# POWER_PCie.net
KiCad netlist of a schematic drawn in Altium Designer
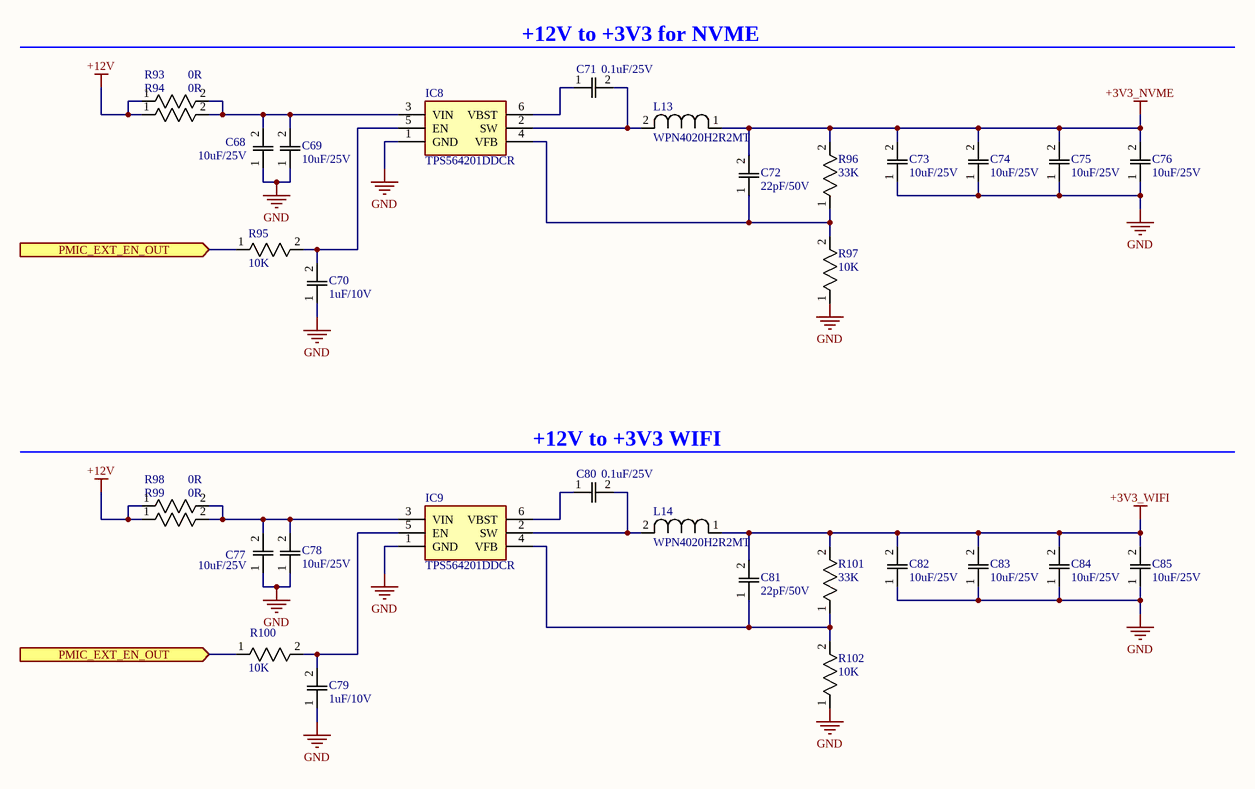
[diagram p0: POWER_PCie.SchDoc]

(export (version "E")
  (design (tool "Eeschema 10.0.6"))
  (components
    (comp (ref "C68")
      (value "10uF/25V")
      (footprint "CAPC220145_88N_KEM")
      (description "10uF / 25 VDC, +85degC, X5R Dielec, +/-10% ¦ KEMET C0805C106K3PACTU 0805")
      (fields
        (field (name "MANUFACTURER") "KEMET")
        (field (name "MANUFACTURER PART NUMBER") "C0805C106K3PACTU")
      )
      (libsource (lib "C0805C106K3PACTU") (part "C0805C106K3PACTU"))
    )
    (comp (ref "C69")
      (value "10uF/25V")
      (footprint "CAPC220145_88N_KEM")
      (description "10uF / 25 VDC, +85degC, X5R Dielec, +/-10% ¦ KEMET C0805C106K3PACTU 0805")
      (fields
        (field (name "MANUFACTURER") "KEMET")
        (field (name "MANUFACTURER PART NUMBER") "C0805C106K3PACTU")
      )
      (libsource (lib "C0805C106K3PACTU") (part "C0805C106K3PACTU"))
    )
    (comp (ref "C70")
      (value "1uF/10V")
      (footprint "CAPC220145_88N_KEM")
      (description "Multilayer Ceramic Capacitors MLCC - SMD/SMT 10V 1uF X7R 0805 10%")
      (fields
        (field (name "MANUFACTURER") "KEMET")
        (field (name "MANUFACTURER PART NUMBER") "C0805C105K8RACTU")
      )
      (libsource (lib "C0805C105K8RACTU") (part "C0805C105K8RACTU"))
    )
    (comp (ref "C71")
      (value "0.1uF/25V")
      (footprint "CAPC220145_88N_KEM")
      (description "0.1uF 25V X7R 10% SMD 0805 125C Plastic T/R")
      (fields
        (field (name "MANUFACTURER") "KEMET")
        (field (name "MANUFACTURER PART NUMBER") "C0805C104K3RACTU")
      )
      (libsource (lib "C0805C104K3RACTU") (part "C0805C104K3RACTU"))
    )
    (comp (ref "C72")
      (value "22pF/50V")
      (footprint "CAPC220145_88N_KEM")
      (description "Cap Ceramic 22pF 50V X7R 5% Pad SMD 0805 125°C T/R")
      (fields
        (field (name "MANUFACTURER") "KEMET")
        (field (name "MANUFACTURER PART NUMBER") "C0805C220J5RACTU")
      )
      (libsource (lib "C0805C220J5RACTU") (part "C0805C220J5RACTU"))
    )
    (comp (ref "C73")
      (value "10uF/25V")
      (footprint "CAPC220145_88N_KEM")
      (description "10uF / 25 VDC, +85degC, X5R Dielec, +/-10% ¦ KEMET C0805C106K3PACTU 0805")
      (fields
        (field (name "MANUFACTURER") "KEMET")
        (field (name "MANUFACTURER PART NUMBER") "C0805C106K3PACTU")
      )
      (libsource (lib "C0805C106K3PACTU") (part "C0805C106K3PACTU"))
    )
    (comp (ref "C74")
      (value "10uF/25V")
      (footprint "CAPC220145_88N_KEM")
      (description "10uF / 25 VDC, +85degC, X5R Dielec, +/-10% ¦ KEMET C0805C106K3PACTU 0805")
      (fields
        (field (name "MANUFACTURER") "KEMET")
        (field (name "MANUFACTURER PART NUMBER") "C0805C106K3PACTU")
      )
      (libsource (lib "C0805C106K3PACTU") (part "C0805C106K3PACTU"))
    )
    (comp (ref "C75")
      (value "10uF/25V")
      (footprint "CAPC220145_88N_KEM")
      (description "10uF / 25 VDC, +85degC, X5R Dielec, +/-10% ¦ KEMET C0805C106K3PACTU 0805")
      (fields
        (field (name "MANUFACTURER") "KEMET")
        (field (name "MANUFACTURER PART NUMBER") "C0805C106K3PACTU")
      )
      (libsource (lib "C0805C106K3PACTU") (part "C0805C106K3PACTU"))
    )
    (comp (ref "C76")
      (value "10uF/25V")
      (footprint "CAPC220145_88N_KEM")
      (description "10uF / 25 VDC, +85degC, X5R Dielec, +/-10% ¦ KEMET C0805C106K3PACTU 0805")
      (fields
        (field (name "MANUFACTURER") "KEMET")
        (field (name "MANUFACTURER PART NUMBER") "C0805C106K3PACTU")
      )
      (libsource (lib "C0805C106K3PACTU") (part "C0805C106K3PACTU"))
    )
    (comp (ref "C77")
      (value "10uF/25V")
      (footprint "CAPC220145_88N_KEM")
      (description "10uF / 25 VDC, +85degC, X5R Dielec, +/-10% ¦ KEMET C0805C106K3PACTU 0805")
      (fields
        (field (name "MANUFACTURER") "KEMET")
        (field (name "MANUFACTURER PART NUMBER") "C0805C106K3PACTU")
      )
      (libsource (lib "C0805C106K3PACTU") (part "C0805C106K3PACTU"))
    )
    (comp (ref "C78")
      (value "10uF/25V")
      (footprint "CAPC220145_88N_KEM")
      (description "10uF / 25 VDC, +85degC, X5R Dielec, +/-10% ¦ KEMET C0805C106K3PACTU 0805")
      (fields
        (field (name "MANUFACTURER") "KEMET")
        (field (name "MANUFACTURER PART NUMBER") "C0805C106K3PACTU")
      )
      (libsource (lib "C0805C106K3PACTU") (part "C0805C106K3PACTU"))
    )
    (comp (ref "C79")
      (value "1uF/10V")
      (footprint "CAPC220145_88N_KEM")
      (description "Multilayer Ceramic Capacitors MLCC - SMD/SMT 10V 1uF X7R 0805 10%")
      (fields
        (field (name "MANUFACTURER") "KEMET")
        (field (name "MANUFACTURER PART NUMBER") "C0805C105K8RACTU")
      )
      (libsource (lib "C0805C105K8RACTU") (part "C0805C105K8RACTU"))
    )
    (comp (ref "C80")
      (value "0.1uF/25V")
      (footprint "CAPC220145_88N_KEM")
      (description "0.1uF 25V X7R 10% SMD 0805 125C Plastic T/R")
      (fields
        (field (name "MANUFACTURER") "KEMET")
        (field (name "MANUFACTURER PART NUMBER") "C0805C104K3RACTU")
      )
      (libsource (lib "C0805C104K3RACTU") (part "C0805C104K3RACTU"))
    )
    (comp (ref "C81")
      (value "22pF/50V")
      (footprint "CAPC220145_88N_KEM")
      (description "Cap Ceramic 22pF 50V X7R 5% Pad SMD 0805 125°C T/R")
      (fields
        (field (name "MANUFACTURER") "KEMET")
        (field (name "MANUFACTURER PART NUMBER") "C0805C220J5RACTU")
      )
      (libsource (lib "C0805C220J5RACTU") (part "C0805C220J5RACTU"))
    )
    (comp (ref "C82")
      (value "10uF/25V")
      (footprint "CAPC220145_88N_KEM")
      (description "10uF / 25 VDC, +85degC, X5R Dielec, +/-10% ¦ KEMET C0805C106K3PACTU 0805")
      (fields
        (field (name "MANUFACTURER") "KEMET")
        (field (name "MANUFACTURER PART NUMBER") "C0805C106K3PACTU")
      )
      (libsource (lib "C0805C106K3PACTU") (part "C0805C106K3PACTU"))
    )
    (comp (ref "C83")
      (value "10uF/25V")
      (footprint "CAPC220145_88N_KEM")
      (description "10uF / 25 VDC, +85degC, X5R Dielec, +/-10% ¦ KEMET C0805C106K3PACTU 0805")
      (fields
        (field (name "MANUFACTURER") "KEMET")
        (field (name "MANUFACTURER PART NUMBER") "C0805C106K3PACTU")
      )
      (libsource (lib "C0805C106K3PACTU") (part "C0805C106K3PACTU"))
    )
    (comp (ref "C84")
      (value "10uF/25V")
      (footprint "CAPC220145_88N_KEM")
      (description "10uF / 25 VDC, +85degC, X5R Dielec, +/-10% ¦ KEMET C0805C106K3PACTU 0805")
      (fields
        (field (name "MANUFACTURER") "KEMET")
        (field (name "MANUFACTURER PART NUMBER") "C0805C106K3PACTU")
      )
      (libsource (lib "C0805C106K3PACTU") (part "C0805C106K3PACTU"))
    )
    (comp (ref "C85")
      (value "10uF/25V")
      (footprint "CAPC220145_88N_KEM")
      (description "10uF / 25 VDC, +85degC, X5R Dielec, +/-10% ¦ KEMET C0805C106K3PACTU 0805")
      (fields
        (field (name "MANUFACTURER") "KEMET")
        (field (name "MANUFACTURER PART NUMBER") "C0805C106K3PACTU")
      )
      (libsource (lib "C0805C106K3PACTU") (part "C0805C106K3PACTU"))
    )
    (comp (ref "IC8")
      (value "TPS564201DDCR")
      (footprint "SamacSys:SOT95P280X110-6N")
      (fields
        (field (name "MOUSER PART NUMBER") "595-TPS564201DDCR")
        (field (name "MANUFACTURER") "Texas Instruments")
      )
      (libsource (lib "SamacSys") (part "TPS564201DDCR"))
    )
    (comp (ref "IC9")
      (value "TPS564201DDCR")
      (footprint "SamacSys:SOT95P280X110-6N")
      (fields
        (field (name "MOUSER PART NUMBER") "595-TPS564201DDCR")
        (field (name "MANUFACTURER") "Texas Instruments")
      )
      (libsource (lib "SamacSys") (part "TPS564201DDCR"))
    )
    (comp (ref "L13")
      (value "WPN4020H2R2MT")
      (footprint "IND_WPN4020H_SNL")
      (description "2.2 µH Shielded Drum Core, Wirewound Inductor 4.3 A 48mOhm Max Nonstandard")
      (fields (field (name "MANUFACTURER") "Sunlord"))
      (libsource (lib "WPN4020H2R2MT") (part "WPN4020H2R2MT"))
    )
    (comp (ref "L14")
      (value "WPN4020H2R2MT")
      (footprint "IND_WPN4020H_SNL")
      (description "2.2 µH Shielded Drum Core, Wirewound Inductor 4.3 A 48mOhm Max Nonstandard")
      (fields (field (name "MANUFACTURER") "Sunlord"))
      (libsource (lib "WPN4020H2R2MT") (part "WPN4020H2R2MT"))
    )
    (comp (ref "R93")
      (value "0R")
      (footprint "SamacSys:ERJ3EKF1000V")
      (description "Zero Ohm Resistor, Jumper, 0603 [1608 Metric], Thick Film, 100 mW, 1 A, Surface Mount")
      (fields
        (field (name "MANUFACTURER_PART_NUMBER") "ERJ-3GEY0R00V")
        (field (name "MOUSER PART NUMBER") "667-ERJ-3GEY0R00V")
      )
      (libsource (lib "SamacSys") (part "ERJ-3GEY0R00V"))
    )
    (comp (ref "R94")
      (value "0R")
      (footprint "SamacSys:ERJ3EKF1000V")
      (description "Zero Ohm Resistor, Jumper, 0603 [1608 Metric], Thick Film, 100 mW, 1 A, Surface Mount")
      (fields
        (field (name "MANUFACTURER_PART_NUMBER") "ERJ-3GEY0R00V")
        (field (name "MOUSER PART NUMBER") "667-ERJ-3GEY0R00V")
      )
      (libsource (lib "SamacSys") (part "ERJ-3GEY0R00V"))
    )
    (comp (ref "R95")
      (value "10K")
      (footprint "SamacSys:ERJ3EKF1000V")
      (description "10K Ohm 5% Res Thick Film 0603  0.1W(1/10W) ±200ppm/C Pad SMD Automotive T/R")
      (fields
        (field (name "MANUFACTURER_PART_NUMBER") "ERJ-3GEYJ103V")
        (field (name "MOUSER PART NUMBER") "667-ERJ-3GEYJ103V")
      )
      (libsource (lib "SamacSys") (part "ERJ-3GEYJ103V"))
    )
    (comp (ref "R96")
      (value "33K")
      (footprint "SamacSys:ERJ3EKF1000V")
      (description "33K Ohm 0603  5% 0.1W(1/10W) +/-200ppm/ßC SMD Automotive T/R")
      (fields
        (field (name "MANUFACTURER_PART_NUMBER") "ERJ-3GEYJ333V")
        (field (name "MOUSER PART NUMBER") "667-ERJ-3GEYJ333V")
      )
      (libsource (lib "SamacSys") (part "ERJ-3GEYJ333V"))
    )
    (comp (ref "R97")
      (value "10K")
      (footprint "SamacSys:ERJ3EKF1000V")
      (description "10K Ohm 5% Res Thick Film 0603  0.1W(1/10W) ±200ppm/C Pad SMD Automotive T/R")
      (fields
        (field (name "MANUFACTURER_PART_NUMBER") "ERJ-3GEYJ103V")
        (field (name "MOUSER PART NUMBER") "667-ERJ-3GEYJ103V")
      )
      (libsource (lib "SamacSys") (part "ERJ-3GEYJ103V"))
    )
    (comp (ref "R98")
      (value "0R")
      (footprint "SamacSys:ERJ3EKF1000V")
      (description "Zero Ohm Resistor, Jumper, 0603 [1608 Metric], Thick Film, 100 mW, 1 A, Surface Mount")
      (fields
        (field (name "MANUFACTURER_PART_NUMBER") "ERJ-3GEY0R00V")
        (field (name "MOUSER PART NUMBER") "667-ERJ-3GEY0R00V")
      )
      (libsource (lib "SamacSys") (part "ERJ-3GEY0R00V"))
    )
    (comp (ref "R99")
      (value "0R")
      (footprint "SamacSys:ERJ3EKF1000V")
      (description "Zero Ohm Resistor, Jumper, 0603 [1608 Metric], Thick Film, 100 mW, 1 A, Surface Mount")
      (fields
        (field (name "MANUFACTURER_PART_NUMBER") "ERJ-3GEY0R00V")
        (field (name "MOUSER PART NUMBER") "667-ERJ-3GEY0R00V")
      )
      (libsource (lib "SamacSys") (part "ERJ-3GEY0R00V"))
    )
    (comp (ref "R100")
      (value "10K")
      (footprint "SamacSys:ERJ3EKF1000V")
      (description "10K Ohm 5% Res Thick Film 0603  0.1W(1/10W) ±200ppm/C Pad SMD Automotive T/R")
      (fields
        (field (name "MANUFACTURER_PART_NUMBER") "ERJ-3GEYJ103V")
        (field (name "MOUSER PART NUMBER") "667-ERJ-3GEYJ103V")
      )
      (libsource (lib "SamacSys") (part "ERJ-3GEYJ103V"))
    )
    (comp (ref "R101")
      (value "33K")
      (footprint "SamacSys:ERJ3EKF1000V")
      (description "33K Ohm 0603  5% 0.1W(1/10W) +/-200ppm/ßC SMD Automotive T/R")
      (fields
        (field (name "MANUFACTURER_PART_NUMBER") "ERJ-3GEYJ333V")
        (field (name "MOUSER PART NUMBER") "667-ERJ-3GEYJ333V")
      )
      (libsource (lib "SamacSys") (part "ERJ-3GEYJ333V"))
    )
    (comp (ref "R102")
      (value "10K")
      (footprint "SamacSys:ERJ3EKF1000V")
      (description "10K Ohm 5% Res Thick Film 0603  0.1W(1/10W) ±200ppm/C Pad SMD Automotive T/R")
      (fields
        (field (name "MANUFACTURER_PART_NUMBER") "ERJ-3GEYJ103V")
        (field (name "MOUSER PART NUMBER") "667-ERJ-3GEYJ103V")
      )
      (libsource (lib "SamacSys") (part "ERJ-3GEYJ103V"))
    )
  )
  (nets
    (net (code "1") (name "+3V3_NVME") (class "Default")
      (node (ref "C72") (pin "2") (pinfunction "2_2") (pintype "passive"))
      (node (ref "C73") (pin "2") (pinfunction "2_2") (pintype "passive"))
      (node (ref "C74") (pin "2") (pinfunction "2_2") (pintype "passive"))
      (node (ref "C75") (pin "2") (pinfunction "2_2") (pintype "passive"))
      (node (ref "C76") (pin "2") (pinfunction "2_2") (pintype "passive"))
      (node (ref "L13") (pin "1") (pinfunction "1_1") (pintype "passive"))
      (node (ref "R96") (pin "2") (pinfunction "2_2") (pintype "passive"))
    )
    (net (code "2") (name "+3V3_WIFI") (class "Default")
      (node (ref "C81") (pin "2") (pinfunction "2_2") (pintype "passive"))
      (node (ref "C82") (pin "2") (pinfunction "2_2") (pintype "passive"))
      (node (ref "C83") (pin "2") (pinfunction "2_2") (pintype "passive"))
      (node (ref "C84") (pin "2") (pinfunction "2_2") (pintype "passive"))
      (node (ref "C85") (pin "2") (pinfunction "2_2") (pintype "passive"))
      (node (ref "L14") (pin "1") (pinfunction "1_1") (pintype "passive"))
      (node (ref "R101") (pin "2") (pinfunction "2_2") (pintype "passive"))
    )
    (net (code "3") (name "+12V") (class "Default")
      (node (ref "R93") (pin "1") (pinfunction "1_1") (pintype "passive"))
      (node (ref "R94") (pin "1") (pinfunction "1_1") (pintype "passive"))
      (node (ref "R98") (pin "1") (pinfunction "1_1") (pintype "passive"))
      (node (ref "R99") (pin "1") (pinfunction "1_1") (pintype "passive"))
    )
    (net (code "4") (name "/PMIC_EXT_EN_OUT") (class "Default")
      (node (ref "R100") (pin "1") (pinfunction "1_1") (pintype "passive"))
      (node (ref "R95") (pin "1") (pinfunction "1_1") (pintype "passive"))
    )
    (net (code "5") (name "GND") (class "Default")
      (node (ref "C68") (pin "1") (pinfunction "1_1") (pintype "passive"))
      (node (ref "C69") (pin "1") (pinfunction "1_1") (pintype "passive"))
      (node (ref "C70") (pin "1") (pinfunction "1_1") (pintype "passive"))
      (node (ref "C73") (pin "1") (pinfunction "1_1") (pintype "passive"))
      (node (ref "C74") (pin "1") (pinfunction "1_1") (pintype "passive"))
      (node (ref "C75") (pin "1") (pinfunction "1_1") (pintype "passive"))
      (node (ref "C76") (pin "1") (pinfunction "1_1") (pintype "passive"))
      (node (ref "C77") (pin "1") (pinfunction "1_1") (pintype "passive"))
      (node (ref "C78") (pin "1") (pinfunction "1_1") (pintype "passive"))
      (node (ref "C79") (pin "1") (pinfunction "1_1") (pintype "passive"))
      (node (ref "C82") (pin "1") (pinfunction "1_1") (pintype "passive"))
      (node (ref "C83") (pin "1") (pinfunction "1_1") (pintype "passive"))
      (node (ref "C84") (pin "1") (pinfunction "1_1") (pintype "passive"))
      (node (ref "C85") (pin "1") (pinfunction "1_1") (pintype "passive"))
      (node (ref "IC8") (pin "1") (pinfunction "GND_1") (pintype "passive"))
      (node (ref "IC9") (pin "1") (pinfunction "GND_1") (pintype "passive"))
      (node (ref "R102") (pin "1") (pinfunction "1_1") (pintype "passive"))
      (node (ref "R97") (pin "1") (pinfunction "1_1") (pintype "passive"))
    )
    (net (code "6") (name "Net-(IC8-EN)") (class "Default")
      (node (ref "C70") (pin "2") (pinfunction "2_2") (pintype "passive"))
      (node (ref "IC8") (pin "5") (pinfunction "EN_5") (pintype "passive"))
      (node (ref "R95") (pin "2") (pinfunction "2_2") (pintype "passive"))
    )
    (net (code "7") (name "Net-(IC8-SW)") (class "Default")
      (node (ref "C71") (pin "2") (pinfunction "2_2") (pintype "passive"))
      (node (ref "IC8") (pin "2") (pinfunction "SW_2") (pintype "passive"))
      (node (ref "L13") (pin "2") (pinfunction "2_2") (pintype "passive"))
    )
    (net (code "8") (name "Net-(IC8-VBST)") (class "Default")
      (node (ref "C71") (pin "1") (pinfunction "1_1") (pintype "passive"))
      (node (ref "IC8") (pin "6") (pinfunction "VBST_6") (pintype "passive"))
    )
    (net (code "9") (name "Net-(IC8-VFB)") (class "Default")
      (node (ref "C72") (pin "1") (pinfunction "1_1") (pintype "passive"))
      (node (ref "IC8") (pin "4") (pinfunction "VFB_4") (pintype "passive"))
      (node (ref "R96") (pin "1") (pinfunction "1_1") (pintype "passive"))
      (node (ref "R97") (pin "2") (pinfunction "2_2") (pintype "passive"))
    )
    (net (code "10") (name "Net-(IC8-VIN)") (class "Default")
      (node (ref "C68") (pin "2") (pinfunction "2_2") (pintype "passive"))
      (node (ref "C69") (pin "2") (pinfunction "2_2") (pintype "passive"))
      (node (ref "IC8") (pin "3") (pinfunction "VIN_3") (pintype "passive"))
      (node (ref "R93") (pin "2") (pinfunction "2_2") (pintype "passive"))
      (node (ref "R94") (pin "2") (pinfunction "2_2") (pintype "passive"))
    )
    (net (code "11") (name "Net-(IC9-EN)") (class "Default")
      (node (ref "C79") (pin "2") (pinfunction "2_2") (pintype "passive"))
      (node (ref "IC9") (pin "5") (pinfunction "EN_5") (pintype "passive"))
      (node (ref "R100") (pin "2") (pinfunction "2_2") (pintype "passive"))
    )
    (net (code "12") (name "Net-(IC9-SW)") (class "Default")
      (node (ref "C80") (pin "2") (pinfunction "2_2") (pintype "passive"))
      (node (ref "IC9") (pin "2") (pinfunction "SW_2") (pintype "passive"))
      (node (ref "L14") (pin "2") (pinfunction "2_2") (pintype "passive"))
    )
    (net (code "13") (name "Net-(IC9-VBST)") (class "Default")
      (node (ref "C80") (pin "1") (pinfunction "1_1") (pintype "passive"))
      (node (ref "IC9") (pin "6") (pinfunction "VBST_6") (pintype "passive"))
    )
    (net (code "14") (name "Net-(IC9-VFB)") (class "Default")
      (node (ref "C81") (pin "1") (pinfunction "1_1") (pintype "passive"))
      (node (ref "IC9") (pin "4") (pinfunction "VFB_4") (pintype "passive"))
      (node (ref "R101") (pin "1") (pinfunction "1_1") (pintype "passive"))
      (node (ref "R102") (pin "2") (pinfunction "2_2") (pintype "passive"))
    )
    (net (code "15") (name "Net-(IC9-VIN)") (class "Default")
      (node (ref "C77") (pin "2") (pinfunction "2_2") (pintype "passive"))
      (node (ref "C78") (pin "2") (pinfunction "2_2") (pintype "passive"))
      (node (ref "IC9") (pin "3") (pinfunction "VIN_3") (pintype "passive"))
      (node (ref "R98") (pin "2") (pinfunction "2_2") (pintype "passive"))
      (node (ref "R99") (pin "2") (pinfunction "2_2") (pintype "passive"))
    )
  )
)
